# TSAL_v1.net
KiCad netlist of a schematic drawn in EAGLE
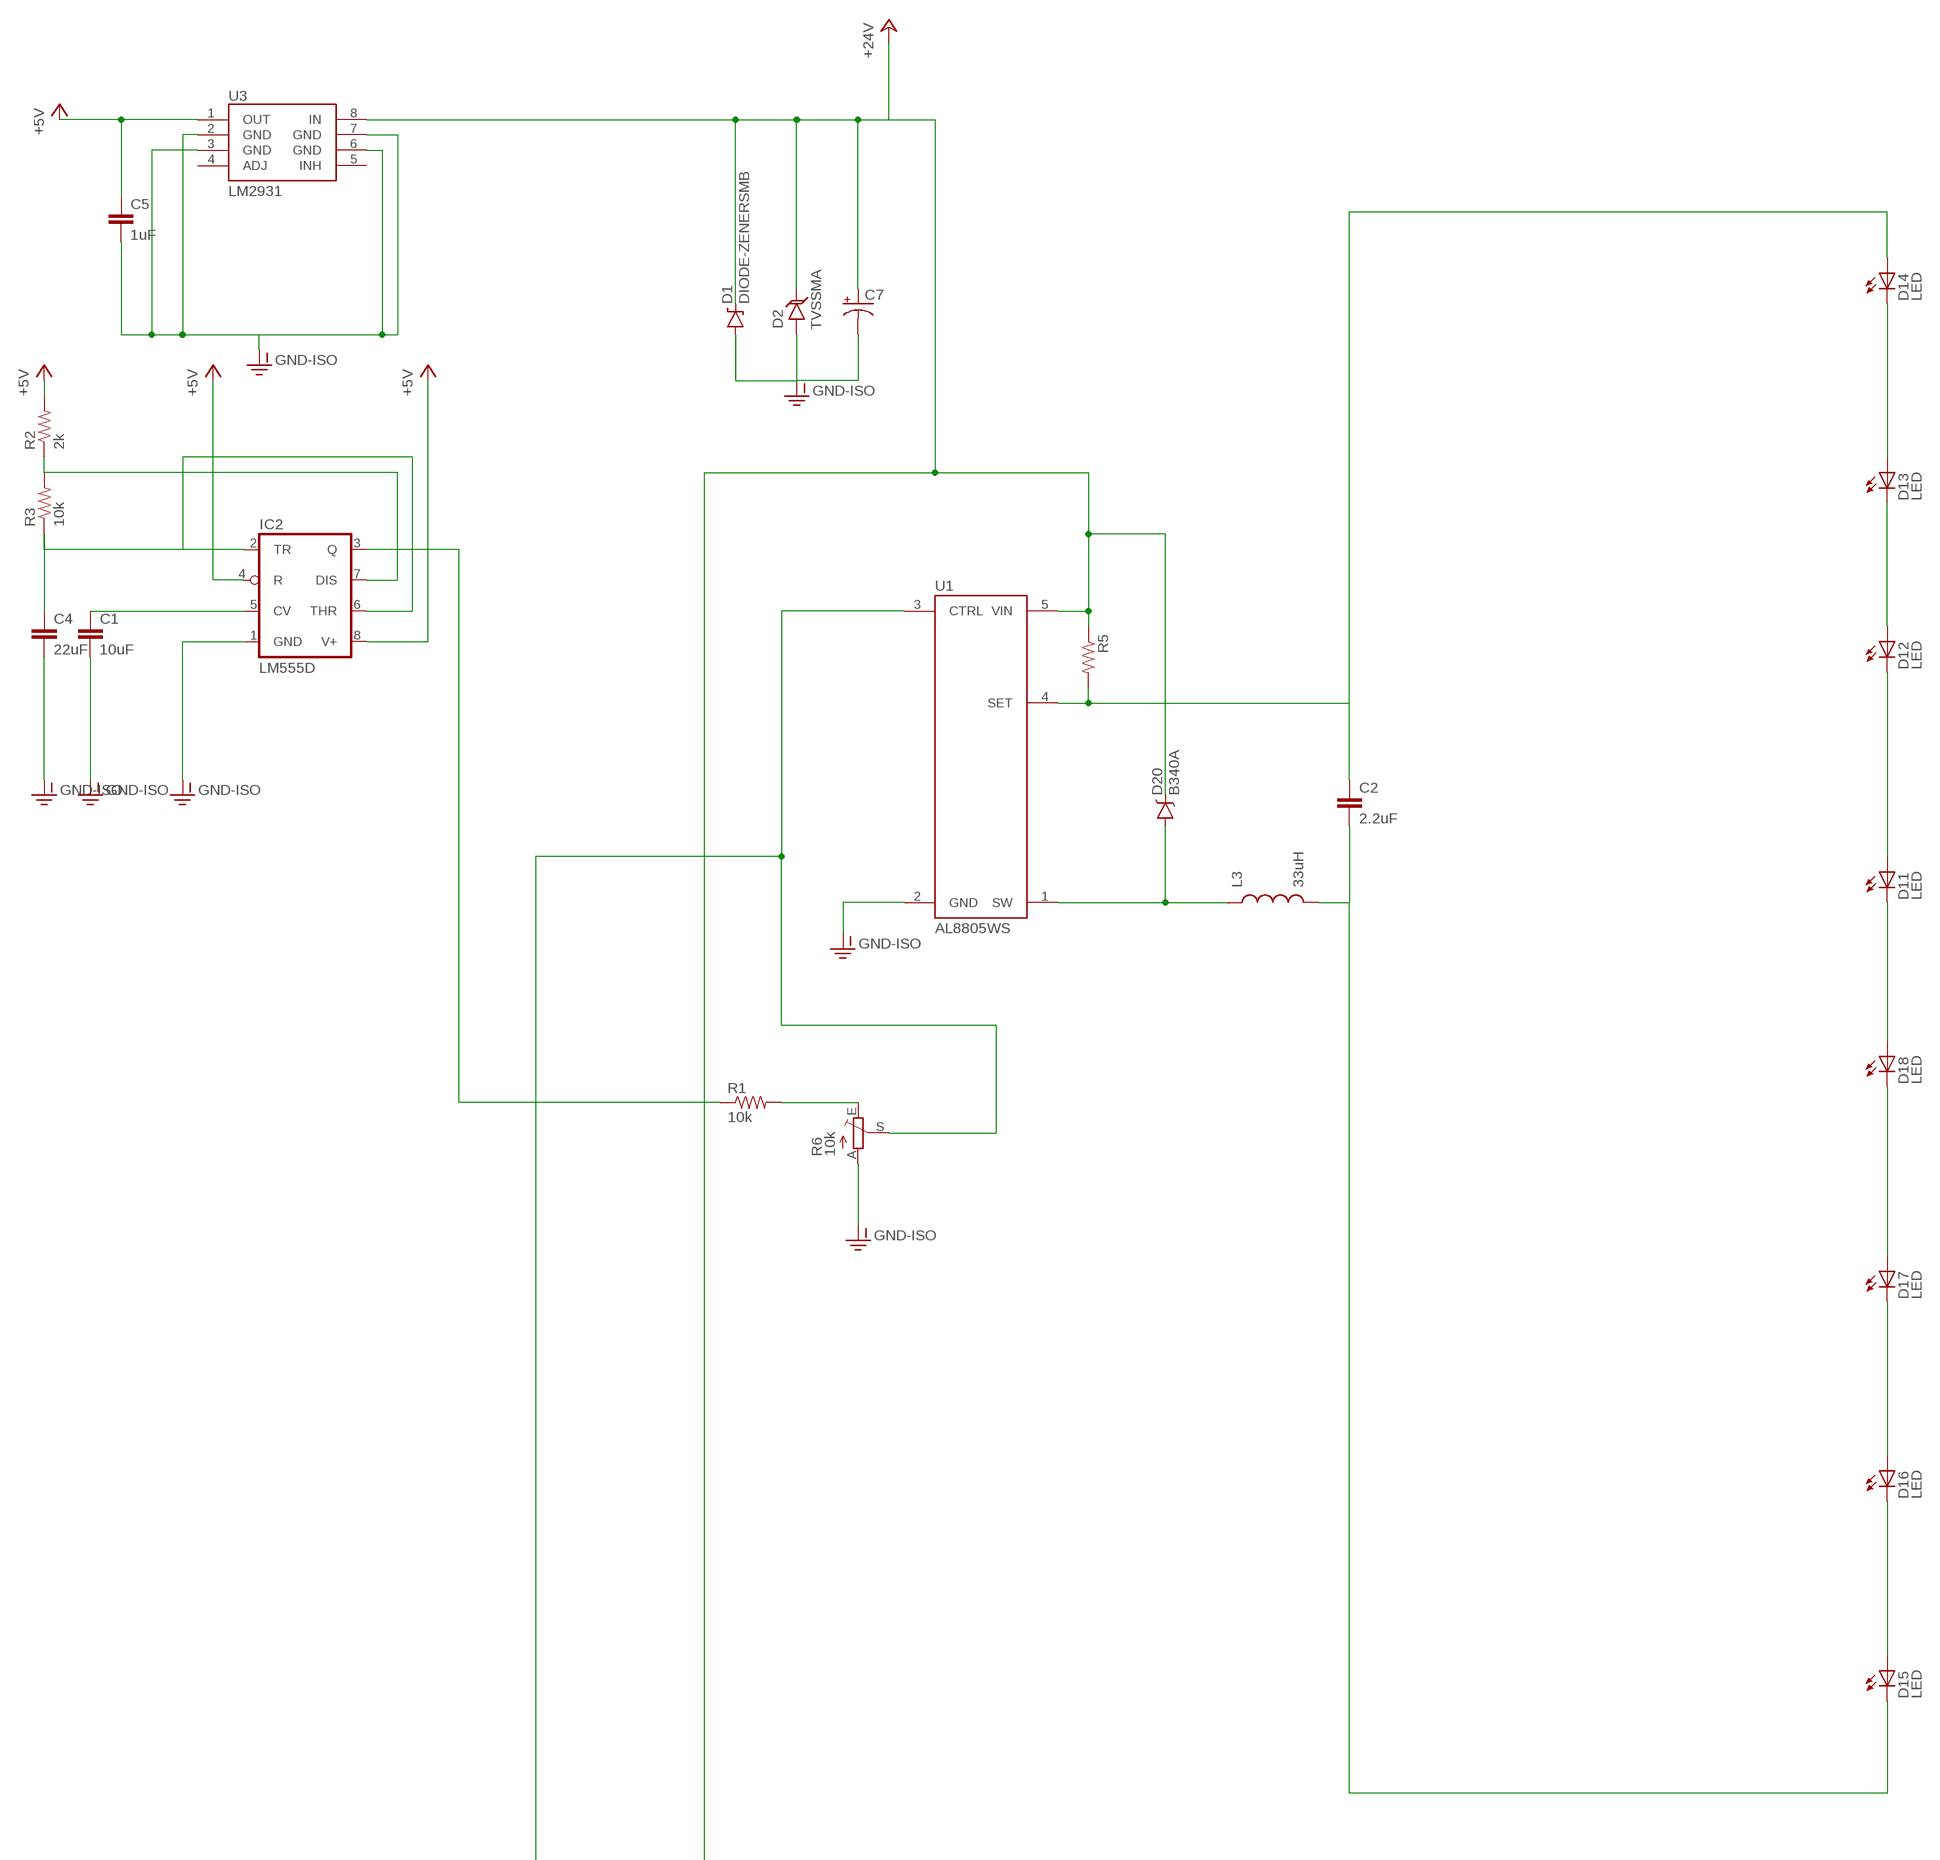
[diagram p0: schematic, sheet 1, part 1 of 2]
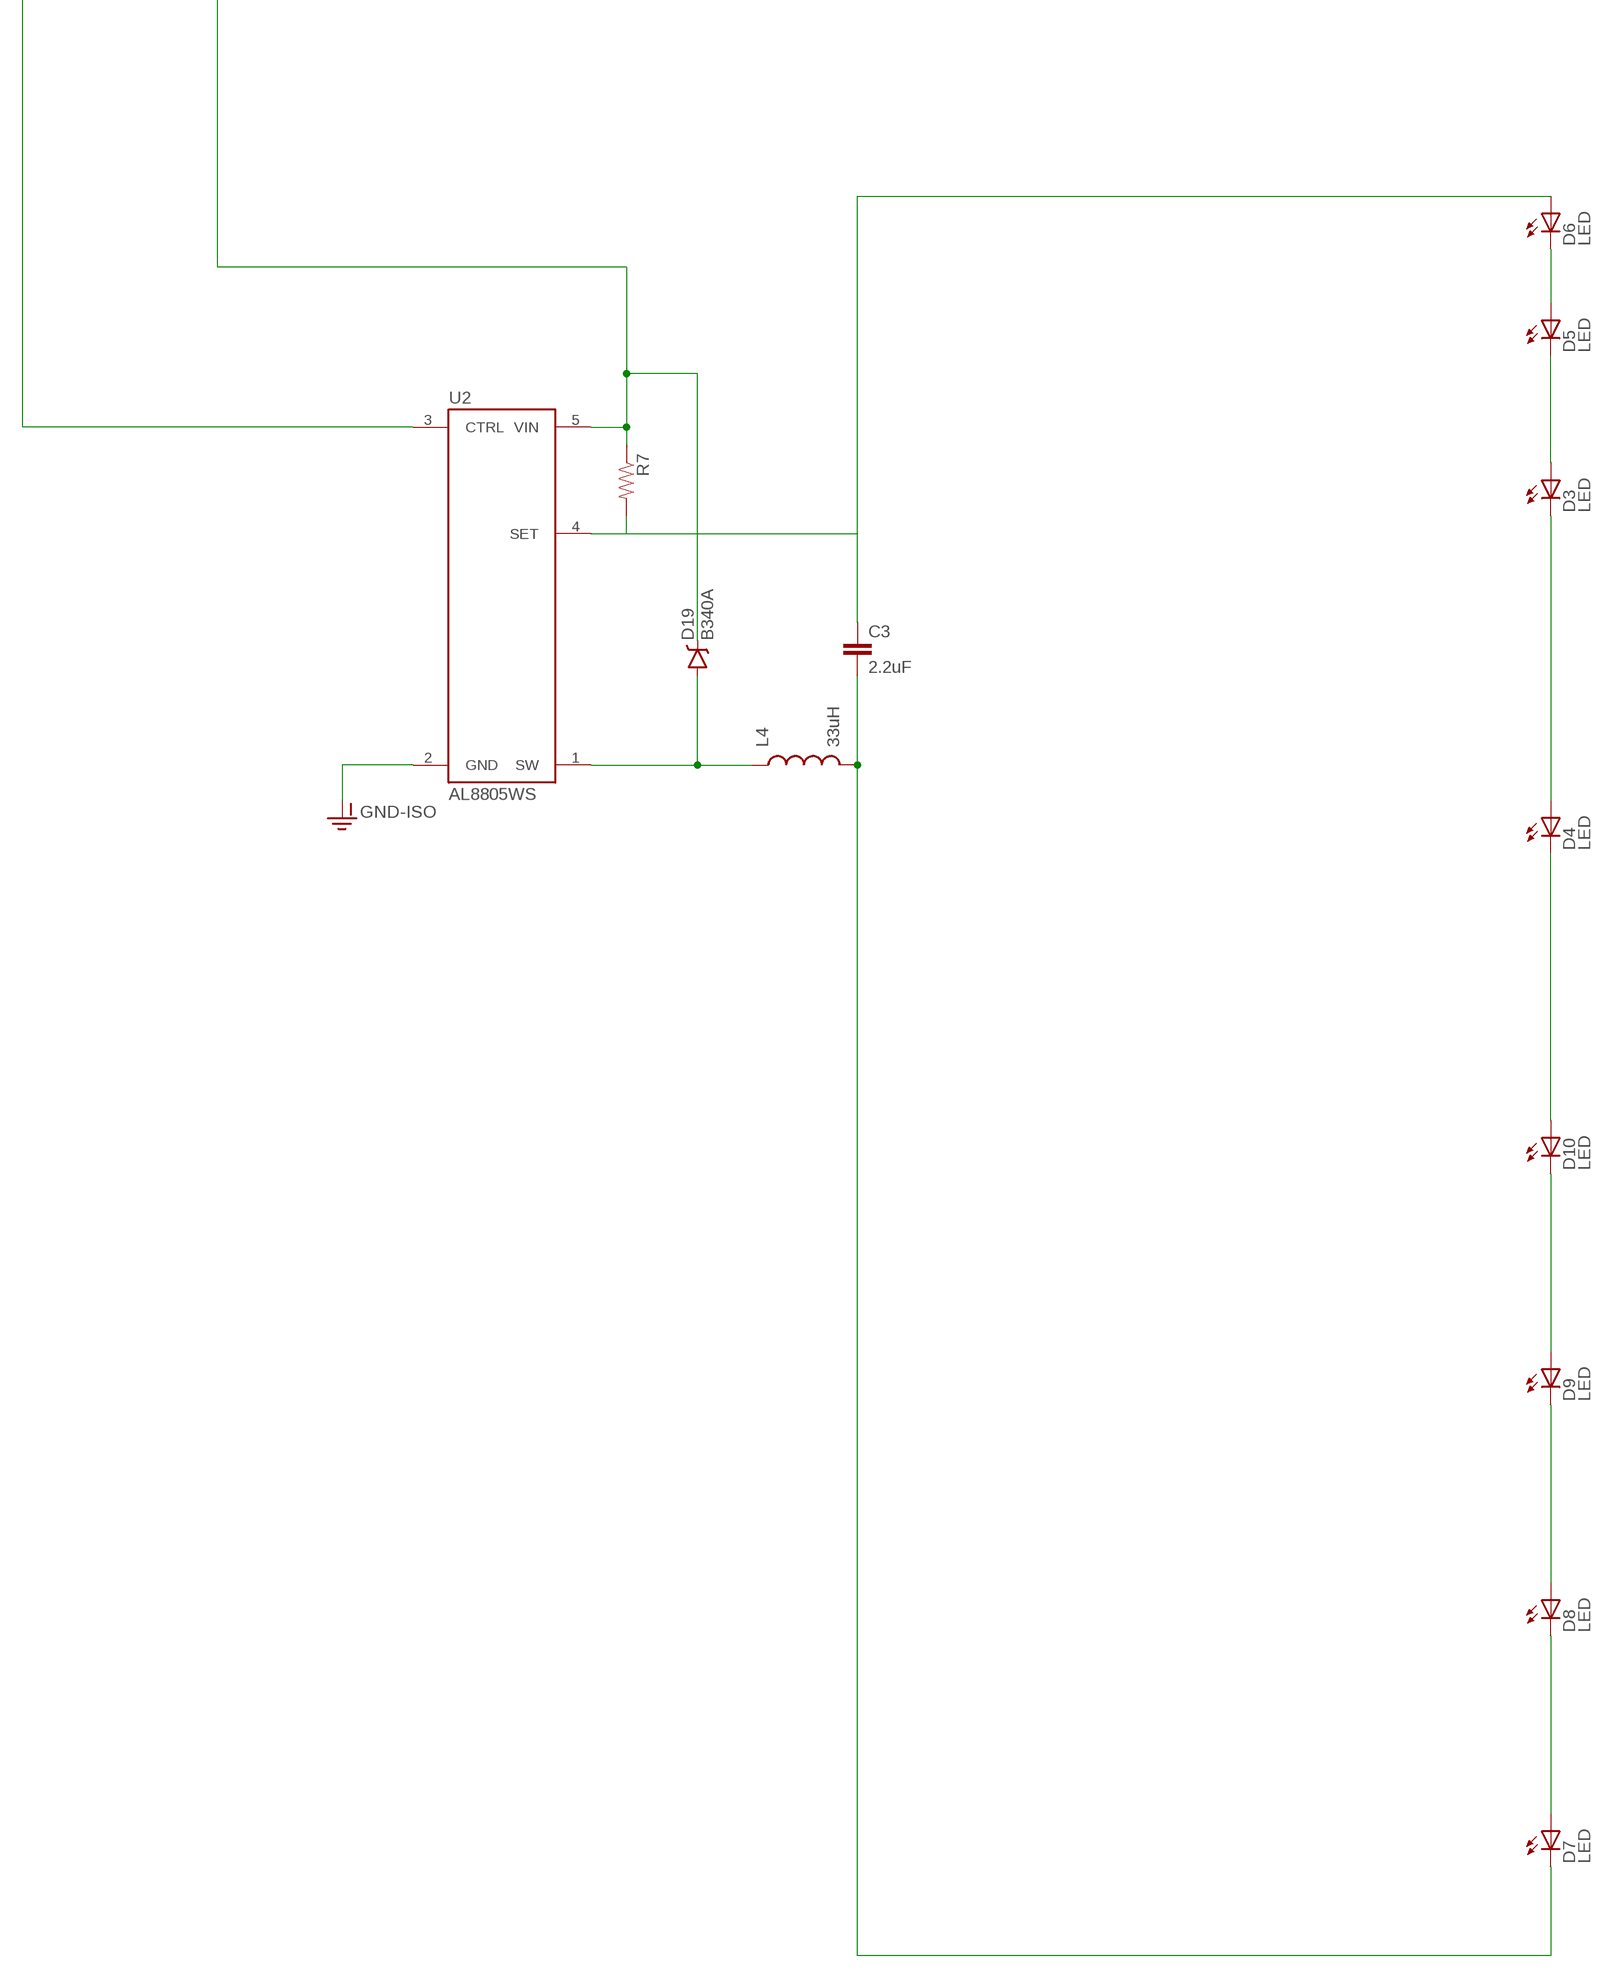
[diagram p1: schematic, sheet 1, part 2 of 2]

(export (version "E")
  (design (tool "Eeschema 10.0.6"))
  (components
    (comp (ref "C1")
      (value "10uF")
      (footprint "eagle-import:0805")
      (libsource (lib "eagle-import") (part "CAP0805"))
    )
    (comp (ref "C2")
      (value "2.2uF")
      (footprint "eagle-import:0805")
      (libsource (lib "eagle-import") (part "CAP0805"))
    )
    (comp (ref "C3")
      (value "2.2uF")
      (footprint "eagle-import:0805")
      (libsource (lib "eagle-import") (part "CAP0805"))
    )
    (comp (ref "C4")
      (value "22uF")
      (footprint "eagle-import:0805")
      (libsource (lib "eagle-import") (part "CAP0805"))
    )
    (comp (ref "C5")
      (value "1uF")
      (footprint "eagle-import:0805")
      (libsource (lib "eagle-import") (part "CAP0805"))
    )
    (comp (ref "C7")
      (value "CAP_POL6032")
      (footprint "eagle-import:EIA6032")
      (libsource (lib "eagle-import") (part "CAP_POL6032"))
    )
    (comp (ref "D1")
      (value "DIODE-ZENERSMB")
      (footprint "eagle-import:SMB-DIODE")
      (libsource (lib "eagle-import") (part "DIODE-ZENERSMB"))
    )
    (comp (ref "D2")
      (value "TVSSMA")
      (footprint "eagle-import:SMA-DIODE")
      (libsource (lib "eagle-import") (part "TVSSMA"))
    )
    (comp (ref "D3")
      (value "LED")
      (footprint "eagle-import:LED-SM")
      (libsource (lib "eagle-import") (part "LED"))
    )
    (comp (ref "D4")
      (value "LED")
      (footprint "eagle-import:LED-SM")
      (libsource (lib "eagle-import") (part "LED"))
    )
    (comp (ref "D5")
      (value "LED")
      (footprint "eagle-import:LED-SM")
      (libsource (lib "eagle-import") (part "LED"))
    )
    (comp (ref "D6")
      (value "LED")
      (footprint "eagle-import:LED-SM")
      (libsource (lib "eagle-import") (part "LED"))
    )
    (comp (ref "D7")
      (value "LED")
      (footprint "eagle-import:LED-SM")
      (libsource (lib "eagle-import") (part "LED"))
    )
    (comp (ref "D8")
      (value "LED")
      (footprint "eagle-import:LED-SM")
      (libsource (lib "eagle-import") (part "LED"))
    )
    (comp (ref "D9")
      (value "LED")
      (footprint "eagle-import:LED-SM")
      (libsource (lib "eagle-import") (part "LED"))
    )
    (comp (ref "D10")
      (value "LED")
      (footprint "eagle-import:LED-SM")
      (libsource (lib "eagle-import") (part "LED"))
    )
    (comp (ref "D11")
      (value "LED")
      (footprint "eagle-import:LED-SM")
      (libsource (lib "eagle-import") (part "LED"))
    )
    (comp (ref "D12")
      (value "LED")
      (footprint "eagle-import:LED-SM")
      (libsource (lib "eagle-import") (part "LED"))
    )
    (comp (ref "D13")
      (value "LED")
      (footprint "eagle-import:LED-SM")
      (libsource (lib "eagle-import") (part "LED"))
    )
    (comp (ref "D14")
      (value "LED")
      (footprint "eagle-import:LED-SM")
      (libsource (lib "eagle-import") (part "LED"))
    )
    (comp (ref "D15")
      (value "LED")
      (footprint "eagle-import:LED-SM")
      (libsource (lib "eagle-import") (part "LED"))
    )
    (comp (ref "D16")
      (value "LED")
      (footprint "eagle-import:LED-SM")
      (libsource (lib "eagle-import") (part "LED"))
    )
    (comp (ref "D17")
      (value "LED")
      (footprint "eagle-import:LED-SM")
      (libsource (lib "eagle-import") (part "LED"))
    )
    (comp (ref "D18")
      (value "LED")
      (footprint "eagle-import:LED-SM")
      (libsource (lib "eagle-import") (part "LED"))
    )
    (comp (ref "D19")
      (value "B340A")
      (footprint "eagle-import:SMA-DIODE")
      (libsource (lib "eagle-import") (part "DIODE-SCHOTTKY-B340A"))
    )
    (comp (ref "D20")
      (value "B340A")
      (footprint "eagle-import:SMA-DIODE")
      (libsource (lib "eagle-import") (part "DIODE-SCHOTTKY-B340A"))
    )
    (comp (ref "IC2")
      (value "LM555D")
      (footprint "eagle-import:SO08")
      (libsource (lib "eagle-import") (part "555DLM"))
    )
    (comp (ref "L3")
      (value "33uH")
      (footprint "eagle-import:SRN6045")
      (libsource (lib "eagle-import") (part "INDUCTORBOURNS_SRN6045"))
    )
    (comp (ref "L4")
      (value "33uH")
      (footprint "eagle-import:SRN6045")
      (libsource (lib "eagle-import") (part "INDUCTORBOURNS_SRN6045"))
    )
    (comp (ref "R1")
      (value "10k")
      (footprint "eagle-import:0805")
      (libsource (lib "eagle-import") (part "RESISTOR0805-RES"))
    )
    (comp (ref "R2")
      (value "2k")
      (footprint "eagle-import:0805")
      (libsource (lib "eagle-import") (part "RESISTOR0805-RES"))
    )
    (comp (ref "R3")
      (value "10k")
      (footprint "eagle-import:0805")
      (libsource (lib "eagle-import") (part "RESISTOR0805-RES"))
    )
    (comp (ref "R5")
      (value "RESISTOR0805-RES")
      (footprint "eagle-import:0805")
      (libsource (lib "eagle-import") (part "RESISTOR0805-RES"))
    )
    (comp (ref "R6")
      (value "10k")
      (footprint "eagle-import:B25P")
      (libsource (lib "eagle-import") (part "TRIM_EU-B25P"))
    )
    (comp (ref "R7")
      (value "RESISTOR0805-RES")
      (footprint "eagle-import:0805")
      (libsource (lib "eagle-import") (part "RESISTOR0805-RES"))
    )
    (comp (ref "U1")
      (value "AL8805WS")
      (footprint "eagle-import:SOT23-5")
      (libsource (lib "eagle-import") (part "AL8805"))
    )
    (comp (ref "U2")
      (value "AL8805WS")
      (footprint "eagle-import:SOT23-5")
      (libsource (lib "eagle-import") (part "AL8805"))
    )
    (comp (ref "U3")
      (value "LM2931")
      (footprint "eagle-import:SO08")
      (libsource (lib "eagle-import") (part "LM2931"))
    )
  )
  (nets
    (net (code "1") (name "+5V") (class "Default")
      (node (ref "C5") (pin "1") (pinfunction "1_1") (pintype "passive"))
      (node (ref "IC2") (pin "4") (pinfunction "R_4") (pintype "input"))
      (node (ref "IC2") (pin "8") (pinfunction "V+_8") (pintype "power_in"))
      (node (ref "R2") (pin "2") (pinfunction "2_2") (pintype "passive"))
      (node (ref "U3") (pin "1") (pinfunction "OUT_1") (pintype "bidirectional"))
    )
    (net (code "2") (name "+24V") (class "Default")
      (node (ref "C7") (pin "P$1") (pinfunction "+_P$1") (pintype "passive"))
      (node (ref "D1") (pin "C") (pinfunction "C_C") (pintype "passive"))
      (node (ref "D19") (pin "C") (pinfunction "C_C") (pintype "passive"))
      (node (ref "D2") (pin "C") (pinfunction "C_C") (pintype "passive"))
      (node (ref "D20") (pin "C") (pinfunction "C_C") (pintype "passive"))
      (node (ref "R5") (pin "1") (pinfunction "1_1") (pintype "passive"))
      (node (ref "R7") (pin "1") (pinfunction "1_1") (pintype "passive"))
      (node (ref "U1") (pin "5") (pinfunction "VIN_5") (pintype "bidirectional"))
      (node (ref "U2") (pin "5") (pinfunction "VIN_5") (pintype "bidirectional"))
      (node (ref "U3") (pin "8") (pinfunction "IN_8") (pintype "bidirectional"))
    )
    (net (code "3") (name "GND-ISO") (class "Default")
      (node (ref "C1") (pin "2") (pinfunction "2_2") (pintype "passive"))
      (node (ref "C4") (pin "2") (pinfunction "2_2") (pintype "passive"))
      (node (ref "C5") (pin "2") (pinfunction "2_2") (pintype "passive"))
      (node (ref "C7") (pin "P$2") (pinfunction "-_P$2") (pintype "passive"))
      (node (ref "D1") (pin "A") (pinfunction "A_A") (pintype "passive"))
      (node (ref "D2") (pin "A") (pinfunction "A_A") (pintype "passive"))
      (node (ref "IC2") (pin "1") (pinfunction "GND_1") (pintype "power_in"))
      (node (ref "R6") (pin "A") (pinfunction "A_A") (pintype "passive"))
      (node (ref "U1") (pin "2") (pinfunction "GND_2") (pintype "bidirectional"))
      (node (ref "U2") (pin "2") (pinfunction "GND_2") (pintype "bidirectional"))
      (node (ref "U3") (pin "2") (pinfunction "GND_2") (pintype "bidirectional"))
      (node (ref "U3") (pin "3") (pinfunction "GND_3") (pintype "bidirectional"))
      (node (ref "U3") (pin "6") (pinfunction "GND_6") (pintype "bidirectional"))
      (node (ref "U3") (pin "7") (pinfunction "GND_7") (pintype "bidirectional"))
    )
    (net (code "4") (name "Net-(C2-Pad2)") (class "Default")
      (node (ref "C2") (pin "2") (pinfunction "2_2") (pintype "passive"))
      (node (ref "D15") (pin "C") (pinfunction "C_C") (pintype "passive"))
      (node (ref "L3") (pin "2") (pinfunction "2_2") (pintype "passive"))
    )
    (net (code "5") (name "Net-(C3-Pad2)") (class "Default")
      (node (ref "C3") (pin "2") (pinfunction "2_2") (pintype "passive"))
      (node (ref "D7") (pin "C") (pinfunction "C_C") (pintype "passive"))
      (node (ref "L4") (pin "2") (pinfunction "2_2") (pintype "passive"))
    )
    (net (code "6") (name "Net-(D3-PadA)") (class "Default")
      (node (ref "D3") (pin "A") (pinfunction "A_A") (pintype "passive"))
      (node (ref "D5") (pin "C") (pinfunction "C_C") (pintype "passive"))
    )
    (net (code "7") (name "Net-(D3-PadC)") (class "Default")
      (node (ref "D3") (pin "C") (pinfunction "C_C") (pintype "passive"))
      (node (ref "D4") (pin "A") (pinfunction "A_A") (pintype "passive"))
    )
    (net (code "8") (name "Net-(D5-PadA)") (class "Default")
      (node (ref "D5") (pin "A") (pinfunction "A_A") (pintype "passive"))
      (node (ref "D6") (pin "C") (pinfunction "C_C") (pintype "passive"))
    )
    (net (code "9") (name "Net-(D7-PadA)") (class "Default")
      (node (ref "D7") (pin "A") (pinfunction "A_A") (pintype "passive"))
      (node (ref "D8") (pin "C") (pinfunction "C_C") (pintype "passive"))
    )
    (net (code "10") (name "Net-(D8-PadA)") (class "Default")
      (node (ref "D8") (pin "A") (pinfunction "A_A") (pintype "passive"))
      (node (ref "D9") (pin "C") (pinfunction "C_C") (pintype "passive"))
    )
    (net (code "11") (name "Net-(D10-PadA)") (class "Default")
      (node (ref "D10") (pin "A") (pinfunction "A_A") (pintype "passive"))
      (node (ref "D4") (pin "C") (pinfunction "C_C") (pintype "passive"))
    )
    (net (code "12") (name "Net-(D10-PadC)") (class "Default")
      (node (ref "D10") (pin "C") (pinfunction "C_C") (pintype "passive"))
      (node (ref "D9") (pin "A") (pinfunction "A_A") (pintype "passive"))
    )
    (net (code "13") (name "Net-(D11-PadA)") (class "Default")
      (node (ref "D11") (pin "A") (pinfunction "A_A") (pintype "passive"))
      (node (ref "D12") (pin "C") (pinfunction "C_C") (pintype "passive"))
    )
    (net (code "14") (name "Net-(D11-PadC)") (class "Default")
      (node (ref "D11") (pin "C") (pinfunction "C_C") (pintype "passive"))
      (node (ref "D18") (pin "A") (pinfunction "A_A") (pintype "passive"))
    )
    (net (code "15") (name "Net-(D12-PadA)") (class "Default")
      (node (ref "D12") (pin "A") (pinfunction "A_A") (pintype "passive"))
      (node (ref "D13") (pin "C") (pinfunction "C_C") (pintype "passive"))
    )
    (net (code "16") (name "Net-(D13-PadA)") (class "Default")
      (node (ref "D13") (pin "A") (pinfunction "A_A") (pintype "passive"))
      (node (ref "D14") (pin "C") (pinfunction "C_C") (pintype "passive"))
    )
    (net (code "17") (name "Net-(D15-PadA)") (class "Default")
      (node (ref "D15") (pin "A") (pinfunction "A_A") (pintype "passive"))
      (node (ref "D16") (pin "C") (pinfunction "C_C") (pintype "passive"))
    )
    (net (code "18") (name "Net-(D16-PadA)") (class "Default")
      (node (ref "D16") (pin "A") (pinfunction "A_A") (pintype "passive"))
      (node (ref "D17") (pin "C") (pinfunction "C_C") (pintype "passive"))
    )
    (net (code "19") (name "Net-(D17-PadA)") (class "Default")
      (node (ref "D17") (pin "A") (pinfunction "A_A") (pintype "passive"))
      (node (ref "D18") (pin "C") (pinfunction "C_C") (pintype "passive"))
    )
    (net (code "20") (name "Net-(IC2-CV)") (class "Default")
      (node (ref "C1") (pin "1") (pinfunction "1_1") (pintype "passive"))
      (node (ref "IC2") (pin "5") (pinfunction "CV_5") (pintype "input"))
    )
    (net (code "21") (name "Net-(IC2-DIS)") (class "Default")
      (node (ref "IC2") (pin "7") (pinfunction "DIS_7") (pintype "input"))
      (node (ref "R2") (pin "1") (pinfunction "1_1") (pintype "passive"))
      (node (ref "R3") (pin "2") (pinfunction "2_2") (pintype "passive"))
    )
    (net (code "22") (name "Net-(IC2-Q)") (class "Default")
      (node (ref "IC2") (pin "3") (pinfunction "Q_3") (pintype "output"))
      (node (ref "R1") (pin "1") (pinfunction "1_1") (pintype "passive"))
    )
    (net (code "23") (name "Net-(IC2-THR)") (class "Default")
      (node (ref "C4") (pin "1") (pinfunction "1_1") (pintype "passive"))
      (node (ref "IC2") (pin "2") (pinfunction "TR_2") (pintype "input"))
      (node (ref "IC2") (pin "6") (pinfunction "THR_6") (pintype "input"))
      (node (ref "R3") (pin "1") (pinfunction "1_1") (pintype "passive"))
    )
    (net (code "24") (name "Net-(R1-Pad2)") (class "Default")
      (node (ref "R1") (pin "2") (pinfunction "2_2") (pintype "passive"))
      (node (ref "R6") (pin "E") (pinfunction "E_E") (pintype "passive"))
    )
    (net (code "25") (name "Net-(U1-CTRL)") (class "Default")
      (node (ref "R6") (pin "S") (pinfunction "S_S") (pintype "passive"))
      (node (ref "U1") (pin "3") (pinfunction "CTRL_3") (pintype "bidirectional"))
      (node (ref "U2") (pin "3") (pinfunction "CTRL_3") (pintype "bidirectional"))
    )
    (net (code "26") (name "Net-(U1-SET)") (class "Default")
      (node (ref "C2") (pin "1") (pinfunction "1_1") (pintype "passive"))
      (node (ref "D14") (pin "A") (pinfunction "A_A") (pintype "passive"))
      (node (ref "R5") (pin "2") (pinfunction "2_2") (pintype "passive"))
      (node (ref "U1") (pin "4") (pinfunction "SET_4") (pintype "bidirectional"))
    )
    (net (code "27") (name "Net-(U1-SW)") (class "Default")
      (node (ref "D20") (pin "A") (pinfunction "A_A") (pintype "passive"))
      (node (ref "L3") (pin "1") (pinfunction "1_1") (pintype "passive"))
      (node (ref "U1") (pin "1") (pinfunction "SW_1") (pintype "bidirectional"))
    )
    (net (code "28") (name "Net-(U2-SET)") (class "Default")
      (node (ref "C3") (pin "1") (pinfunction "1_1") (pintype "passive"))
      (node (ref "D6") (pin "A") (pinfunction "A_A") (pintype "passive"))
      (node (ref "R7") (pin "2") (pinfunction "2_2") (pintype "passive"))
      (node (ref "U2") (pin "4") (pinfunction "SET_4") (pintype "bidirectional"))
    )
    (net (code "29") (name "Net-(U2-SW)") (class "Default")
      (node (ref "D19") (pin "A") (pinfunction "A_A") (pintype "passive"))
      (node (ref "L4") (pin "1") (pinfunction "1_1") (pintype "passive"))
      (node (ref "U2") (pin "1") (pinfunction "SW_1") (pintype "bidirectional"))
    )
    (net (code "30") (name "unconnected-(U3-ADJ-Pad4)") (class "Default")
      (node (ref "U3") (pin "4") (pinfunction "ADJ_4") (pintype "bidirectional"))
    )
    (net (code "31") (name "unconnected-(U3-INH-Pad5)") (class "Default")
      (node (ref "U3") (pin "5") (pinfunction "INH_5") (pintype "bidirectional"))
    )
  )
)
